# Tracer-DIY.net
KiCad netlist of a schematic drawn in EasyEDA Pro
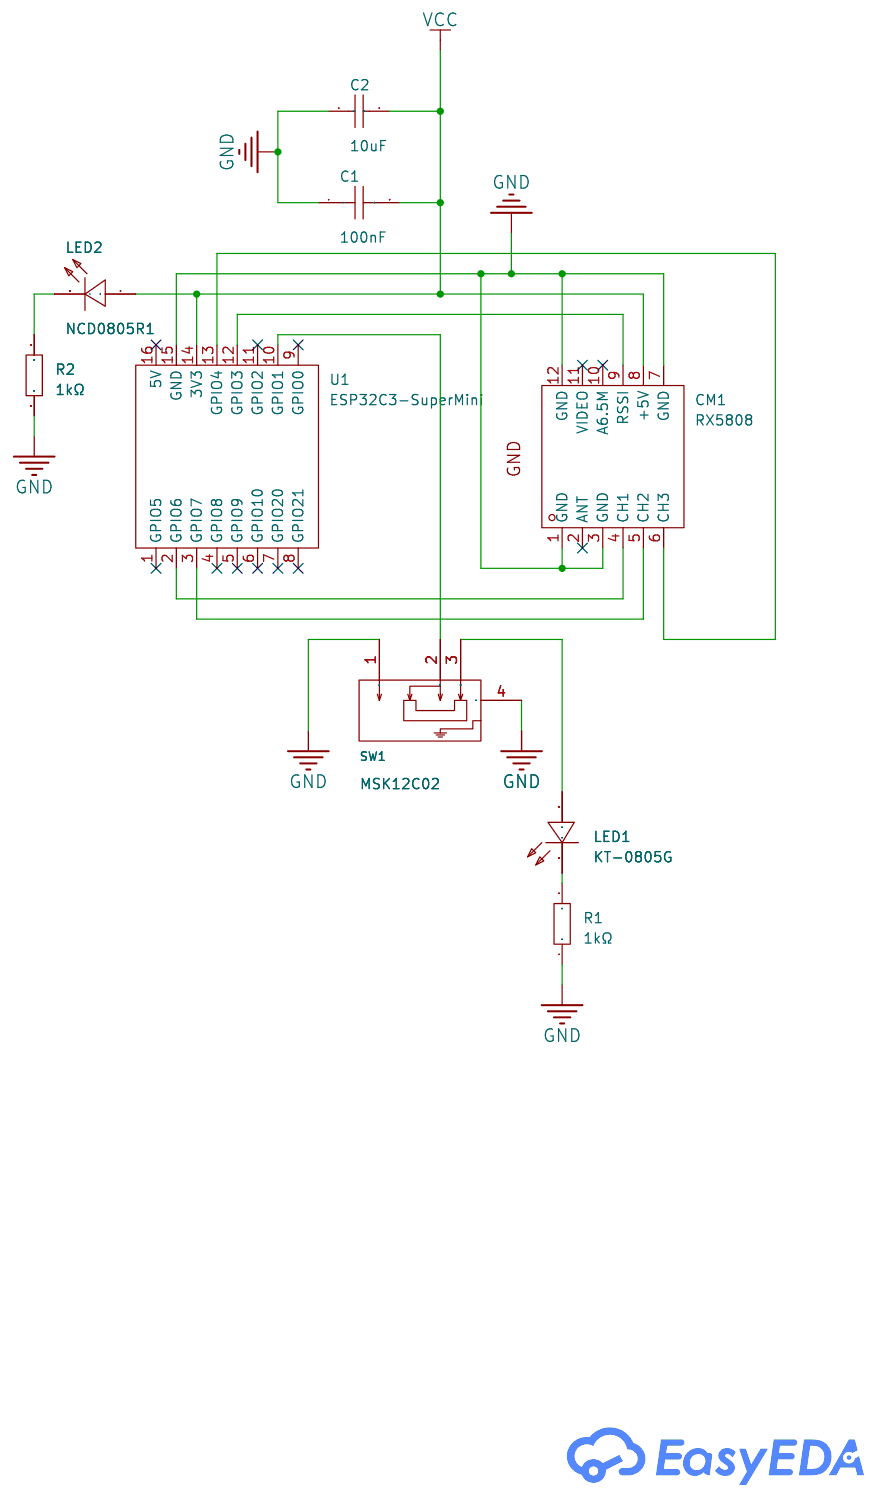
[diagram p0: schematic sheet]

(export (version "E")
  (design (tool "Eeschema 10.0.6"))
  (components
    (comp (ref "C1")
      (value "100nF")
      (footprint "easyedapro:C0402")
      (description "Capacitance:100nF Tolerance:±10% Tolerance:±10% Voltage Rating:50V Temperature Coefficient:X7R")
      (fields
        (field (name "Manufacturer Part") "CL05B104KB54PNC")
        (field (name "Manufacturer") "SAMSUNG(三星)")
      )
      (libsource (lib "easyedapro") (part "CL05B104KB54PNC"))
    )
    (comp (ref "C2")
      (value "10uF")
      (footprint "easyedapro:C0402")
      (description "Capacitance:10uF Tolerance:±20% Tolerance:±20% Voltage Rating:6.3V Temperature Coefficient:X5R")
      (fields
        (field (name "Manufacturer Part") "CL05A106MQ5NUNC")
        (field (name "Manufacturer") "SAMSUNG(三星)")
      )
      (libsource (lib "easyedapro") (part "CL05A106MQ5NUNC"))
    )
    (comp (ref "CM1")
      (value "RX5808")
      (footprint "easyedapro:COMM-SMD_12P_RX5808")
      (libsource (lib "easyedapro") (part "RX5808"))
    )
    (comp (ref "LED1")
      (value "KT-0805G")
      (footprint "easyedapro:LED0805-R-RD")
      (fields (field (name "Manufacturer") "KENTO"))
      (libsource (lib "easyedapro") (part "0805G (Green)"))
    )
    (comp (ref "LED2")
      (value "NCD0805R1")
      (footprint "easyedapro:LED0805-R-RD")
      (fields (field (name "Manufacturer") "国星光电"))
      (libsource (lib "easyedapro") (part "FC-2012HRK-620D"))
    )
    (comp (ref "R1")
      (value "1kΩ")
      (footprint "easyedapro:R0402")
      (fields
        (field (name "Manufacturer Part") "0402WGF1001TCE")
        (field (name "Manufacturer") "UNI-ROYAL(厚声)")
      )
      (libsource (lib "easyedapro") (part "0402WGF1001TCE"))
    )
    (comp (ref "R2")
      (value "1kΩ")
      (footprint "easyedapro:R0402")
      (fields
        (field (name "Manufacturer Part") "0402WGF1001TCE")
        (field (name "Manufacturer") "UNI-ROYAL(厚声)")
      )
      (libsource (lib "easyedapro") (part "0402WGF1001TCE"))
    )
    (comp (ref "SW1")
      (value "MSK12C02")
      (footprint "easyedapro:SW-TH_MSK12C02")
      (fields (field (name "Manufacturer") "SHOU HAN(首韩)"))
      (libsource (lib "easyedapro") (part "MSK12C02"))
    )
    (comp (ref "U1")
      (value "ESP32C3-SuperMini")
      (footprint "easyedapro:COMM-SMD_16P-L22.5-W18.0-P2.54-TL")
      (libsource (lib "easyedapro") (part "ESP32C3-SUPERMINI"))
    )
  )
  (nets
    (net (code "1") (name "GND") (class "Default")
      (node (ref "C1") (pin "1") (pinfunction "1_1") (pintype "input"))
      (node (ref "C2") (pin "1") (pinfunction "1_1") (pintype "input"))
      (node (ref "CM1") (pin "1") (pinfunction "GND_1") (pintype "input"))
      (node (ref "CM1") (pin "12") (pinfunction "GND_12") (pintype "input"))
      (node (ref "CM1") (pin "3") (pinfunction "GND_3") (pintype "input"))
      (node (ref "CM1") (pin "7") (pinfunction "GND_7") (pintype "input"))
      (node (ref "R1") (pin "1") (pinfunction "1_1") (pintype "input"))
      (node (ref "R2") (pin "2") (pinfunction "2_2") (pintype "input"))
      (node (ref "SW1") (pin "1") (pinfunction "1_1") (pintype "input"))
      (node (ref "SW1") (pin "4") (pinfunction "4_4") (pintype "input"))
      (node (ref "U1") (pin "15") (pinfunction "GND_15") (pintype "unspecified"))
    )
    (net (code "2") (name "Net-(CM1-CH1)") (class "Default")
      (node (ref "CM1") (pin "4") (pinfunction "CH1_4") (pintype "input"))
      (node (ref "U1") (pin "2") (pinfunction "GPIO6_2") (pintype "unspecified"))
    )
    (net (code "3") (name "Net-(CM1-CH2)") (class "Default")
      (node (ref "CM1") (pin "5") (pinfunction "CH2_5") (pintype "input"))
      (node (ref "U1") (pin "3") (pinfunction "GPIO7_3") (pintype "unspecified"))
    )
    (net (code "4") (name "Net-(CM1-CH3)") (class "Default")
      (node (ref "CM1") (pin "6") (pinfunction "CH3_6") (pintype "input"))
      (node (ref "U1") (pin "13") (pinfunction "GPIO4_13") (pintype "unspecified"))
    )
    (net (code "5") (name "Net-(CM1-RSSI)") (class "Default")
      (node (ref "CM1") (pin "9") (pinfunction "RSSI_9") (pintype "input"))
      (node (ref "U1") (pin "12") (pinfunction "GPIO3_12") (pintype "unspecified"))
    )
    (net (code "6") (name "Net-(LED1-A)") (class "Default")
      (node (ref "LED1") (pin "1") (pinfunction "A_1") (pintype "unspecified"))
      (node (ref "SW1") (pin "3") (pinfunction "3_3") (pintype "input"))
    )
    (net (code "7") (name "Net-(LED1-K)") (class "Default")
      (node (ref "LED1") (pin "2") (pinfunction "K_2") (pintype "unspecified"))
      (node (ref "R1") (pin "2") (pinfunction "2_2") (pintype "input"))
    )
    (net (code "8") (name "Net-(LED2--)") (class "Default")
      (node (ref "LED2") (pin "2") (pinfunction "-_2") (pintype "unspecified"))
      (node (ref "R2") (pin "1") (pinfunction "1_1") (pintype "input"))
    )
    (net (code "9") (name "Net-(U1-GPIO1)") (class "Default")
      (node (ref "SW1") (pin "2") (pinfunction "2_2") (pintype "input"))
      (node (ref "U1") (pin "10") (pinfunction "GPIO1_10") (pintype "unspecified"))
    )
    (net (code "10") (name "VCC") (class "Default")
      (node (ref "C1") (pin "2") (pinfunction "2_2") (pintype "input"))
      (node (ref "C2") (pin "2") (pinfunction "2_2") (pintype "input"))
      (node (ref "CM1") (pin "8") (pinfunction "+5V_8") (pintype "input"))
      (node (ref "LED2") (pin "1") (pinfunction "+_1") (pintype "unspecified"))
      (node (ref "U1") (pin "14") (pinfunction "3V3_14") (pintype "unspecified"))
    )
    (net (code "11") (name "unconnected-(CM1-A6.5M-Pad10)") (class "Default")
      (node (ref "CM1") (pin "10") (pinfunction "A6.5M_10") (pintype "input+no_connect"))
    )
    (net (code "12") (name "unconnected-(CM1-ANT-Pad2)") (class "Default")
      (node (ref "CM1") (pin "2") (pinfunction "ANT_2") (pintype "input+no_connect"))
    )
    (net (code "13") (name "unconnected-(CM1-VIDEO-Pad11)") (class "Default")
      (node (ref "CM1") (pin "11") (pinfunction "VIDEO_11") (pintype "input+no_connect"))
    )
    (net (code "14") (name "unconnected-(U1-5V-Pad16)") (class "Default")
      (node (ref "U1") (pin "16") (pinfunction "5V_16") (pintype "unspecified+no_connect"))
    )
    (net (code "15") (name "unconnected-(U1-GPIO0-Pad9)") (class "Default")
      (node (ref "U1") (pin "9") (pinfunction "GPIO0_9") (pintype "unspecified+no_connect"))
    )
    (net (code "16") (name "unconnected-(U1-GPIO2-Pad11)") (class "Default")
      (node (ref "U1") (pin "11") (pinfunction "GPIO2_11") (pintype "unspecified+no_connect"))
    )
    (net (code "17") (name "unconnected-(U1-GPIO5-Pad1)") (class "Default")
      (node (ref "U1") (pin "1") (pinfunction "GPIO5_1") (pintype "unspecified+no_connect"))
    )
    (net (code "18") (name "unconnected-(U1-GPIO8-Pad4)") (class "Default")
      (node (ref "U1") (pin "4") (pinfunction "GPIO8_4") (pintype "unspecified+no_connect"))
    )
    (net (code "19") (name "unconnected-(U1-GPIO9-Pad5)") (class "Default")
      (node (ref "U1") (pin "5") (pinfunction "GPIO9_5") (pintype "unspecified+no_connect"))
    )
    (net (code "20") (name "unconnected-(U1-GPIO10-Pad6)") (class "Default")
      (node (ref "U1") (pin "6") (pinfunction "GPIO10_6") (pintype "unspecified+no_connect"))
    )
    (net (code "21") (name "unconnected-(U1-GPIO20-Pad7)") (class "Default")
      (node (ref "U1") (pin "7") (pinfunction "GPIO20_7") (pintype "unspecified+no_connect"))
    )
    (net (code "22") (name "unconnected-(U1-GPIO21-Pad8)") (class "Default")
      (node (ref "U1") (pin "8") (pinfunction "GPIO21_8") (pintype "unspecified+no_connect"))
    )
  )
)
